# adaptateur_fusible.net
KiCad netlist of a schematic drawn in EAGLE
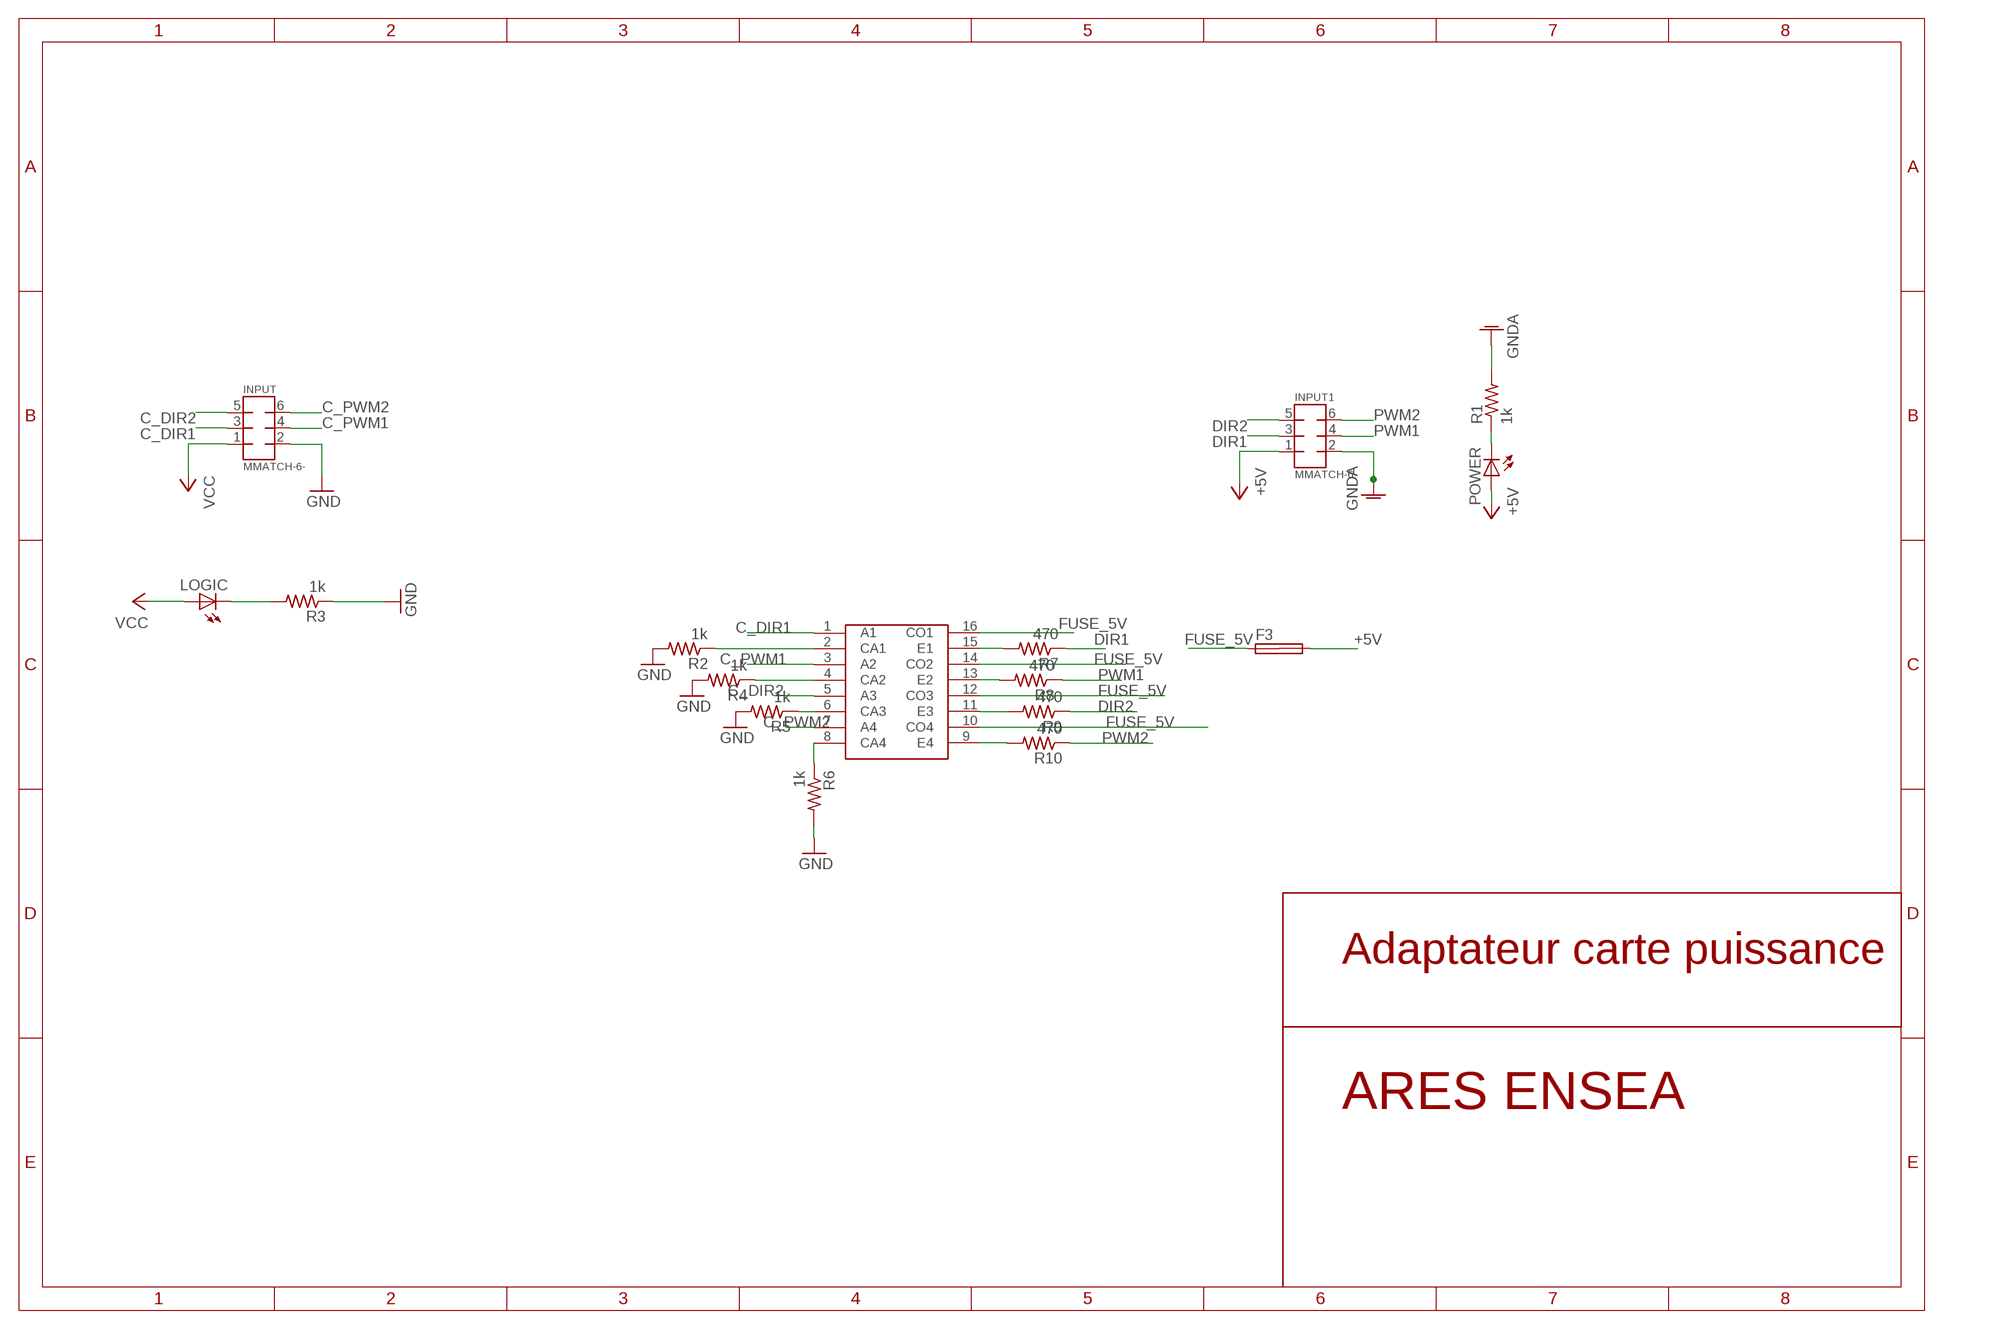
[diagram p0: schematic, sheet 1]

(export (version "E")
  (design (tool "Eeschema 10.0.6"))
  (components
    (comp (ref "F3")
      (value "SHK20Q")
      (footprint "eagle-import:SHK20Q")
      (libsource (lib "eagle-import") (part "SHK20Q"))
    )
    (comp (ref "INPUT")
      (value "MMATCH-6-")
      (footprint "eagle-import:AMP-215079-6")
      (libsource (lib "eagle-import") (part "MMATCH-6-"))
    )
    (comp (ref "INPUT1")
      (value "MMATCH-6-")
      (footprint "eagle-import:AMP-215079-6")
      (libsource (lib "eagle-import") (part "MMATCH-6-"))
    )
    (comp (ref "LOGIC")
      (value "LEDSML0805")
      (footprint "eagle-import:SML0805")
      (libsource (lib "eagle-import") (part "LEDSML0805"))
    )
    (comp (ref "POWER")
      (value "LEDSML0805")
      (footprint "eagle-import:SML0805")
      (libsource (lib "eagle-import") (part "LEDSML0805"))
    )
    (comp (ref "R1")
      (value "1k")
      (footprint "eagle-import:M0805")
      (libsource (lib "eagle-import") (part "R-US_M0805"))
    )
    (comp (ref "R2")
      (value "1k")
      (footprint "eagle-import:M0805")
      (libsource (lib "eagle-import") (part "R-US_M0805"))
    )
    (comp (ref "R3")
      (value "1k")
      (footprint "eagle-import:M0805")
      (libsource (lib "eagle-import") (part "R-US_M0805"))
    )
    (comp (ref "R4")
      (value "1k")
      (footprint "eagle-import:M0805")
      (libsource (lib "eagle-import") (part "R-US_M0805"))
    )
    (comp (ref "R5")
      (value "1k")
      (footprint "eagle-import:M0805")
      (libsource (lib "eagle-import") (part "R-US_M0805"))
    )
    (comp (ref "R6")
      (value "1k")
      (footprint "eagle-import:M0805")
      (libsource (lib "eagle-import") (part "R-US_M0805"))
    )
    (comp (ref "R7")
      (value "470")
      (footprint "eagle-import:M0805")
      (libsource (lib "eagle-import") (part "R-US_M0805"))
    )
    (comp (ref "R8")
      (value "470")
      (footprint "eagle-import:M0805")
      (libsource (lib "eagle-import") (part "R-US_M0805"))
    )
    (comp (ref "R9")
      (value "470")
      (footprint "eagle-import:M0805")
      (libsource (lib "eagle-import") (part "R-US_M0805"))
    )
    (comp (ref "R10")
      (value "470")
      (footprint "eagle-import:M0805")
      (libsource (lib "eagle-import") (part "R-US_M0805"))
    )
    (comp (ref "U$1")
      (value "ACPL-244")
      (footprint "eagle-import:ACPL-244")
      (libsource (lib "eagle-import") (part "ACPL-244"))
    )
  )
  (nets
    (net (code "1") (name "+5V") (class "Default")
      (node (ref "F3") (pin "2A") (pinfunction "2A_2A") (pintype "passive"))
      (node (ref "INPUT1") (pin "1") (pinfunction "3_1") (pintype "bidirectional"))
      (node (ref "POWER") (pin "A") (pinfunction "A_A") (pintype "passive"))
    )
    (net (code "2") (name "/C_DIR1") (class "Default")
      (node (ref "INPUT") (pin "3") (pinfunction "5_3") (pintype "bidirectional"))
      (node (ref "U$1") (pin "1") (pinfunction "A1_1") (pintype "bidirectional"))
    )
    (net (code "3") (name "/C_DIR2") (class "Default")
      (node (ref "INPUT") (pin "5") (pinfunction "7_5") (pintype "bidirectional"))
      (node (ref "U$1") (pin "5") (pinfunction "A3_5") (pintype "bidirectional"))
    )
    (net (code "4") (name "/C_PWM1") (class "Default")
      (node (ref "INPUT") (pin "4") (pinfunction "6_4") (pintype "bidirectional"))
      (node (ref "U$1") (pin "3") (pinfunction "A2_3") (pintype "bidirectional"))
    )
    (net (code "5") (name "/C_PWM2") (class "Default")
      (node (ref "INPUT") (pin "6") (pinfunction "8_6") (pintype "bidirectional"))
      (node (ref "U$1") (pin "7") (pinfunction "A4_7") (pintype "bidirectional"))
    )
    (net (code "6") (name "/DIR1") (class "Default")
      (node (ref "INPUT1") (pin "3") (pinfunction "5_3") (pintype "bidirectional"))
      (node (ref "R7") (pin "1") (pinfunction "1_1") (pintype "passive"))
    )
    (net (code "7") (name "/DIR2") (class "Default")
      (node (ref "INPUT1") (pin "5") (pinfunction "7_5") (pintype "bidirectional"))
      (node (ref "R9") (pin "1") (pinfunction "1_1") (pintype "passive"))
    )
    (net (code "8") (name "/FUSE_5V") (class "Default")
      (node (ref "F3") (pin "1A") (pinfunction "1A_1A") (pintype "passive"))
      (node (ref "U$1") (pin "10") (pinfunction "CO4_10") (pintype "bidirectional"))
      (node (ref "U$1") (pin "12") (pinfunction "CO3_12") (pintype "bidirectional"))
      (node (ref "U$1") (pin "14") (pinfunction "CO2_14") (pintype "bidirectional"))
      (node (ref "U$1") (pin "16") (pinfunction "CO1_16") (pintype "bidirectional"))
    )
    (net (code "9") (name "/PWM1") (class "Default")
      (node (ref "INPUT1") (pin "4") (pinfunction "6_4") (pintype "bidirectional"))
      (node (ref "R8") (pin "1") (pinfunction "1_1") (pintype "passive"))
    )
    (net (code "10") (name "/PWM2") (class "Default")
      (node (ref "INPUT1") (pin "6") (pinfunction "8_6") (pintype "bidirectional"))
      (node (ref "R10") (pin "1") (pinfunction "1_1") (pintype "passive"))
    )
    (net (code "11") (name "GND") (class "Default")
      (node (ref "INPUT") (pin "2") (pinfunction "4_2") (pintype "bidirectional"))
      (node (ref "R2") (pin "2") (pinfunction "2_2") (pintype "passive"))
      (node (ref "R3") (pin "1") (pinfunction "1_1") (pintype "passive"))
      (node (ref "R4") (pin "2") (pinfunction "2_2") (pintype "passive"))
      (node (ref "R5") (pin "2") (pinfunction "2_2") (pintype "passive"))
      (node (ref "R6") (pin "2") (pinfunction "2_2") (pintype "passive"))
    )
    (net (code "12") (name "GNDA") (class "Default")
      (node (ref "INPUT1") (pin "2") (pinfunction "4_2") (pintype "bidirectional"))
      (node (ref "R1") (pin "2") (pinfunction "2_2") (pintype "passive"))
    )
    (net (code "13") (name "Net-(LOGIC-PadC)") (class "Default")
      (node (ref "LOGIC") (pin "C") (pinfunction "C_C") (pintype "passive"))
      (node (ref "R3") (pin "2") (pinfunction "2_2") (pintype "passive"))
    )
    (net (code "14") (name "Net-(POWER-PadC)") (class "Default")
      (node (ref "POWER") (pin "C") (pinfunction "C_C") (pintype "passive"))
      (node (ref "R1") (pin "1") (pinfunction "1_1") (pintype "passive"))
    )
    (net (code "15") (name "Net-(U$1-CA1)") (class "Default")
      (node (ref "R2") (pin "1") (pinfunction "1_1") (pintype "passive"))
      (node (ref "U$1") (pin "2") (pinfunction "CA1_2") (pintype "bidirectional"))
    )
    (net (code "16") (name "Net-(U$1-CA2)") (class "Default")
      (node (ref "R4") (pin "1") (pinfunction "1_1") (pintype "passive"))
      (node (ref "U$1") (pin "4") (pinfunction "CA2_4") (pintype "bidirectional"))
    )
    (net (code "17") (name "Net-(U$1-CA3)") (class "Default")
      (node (ref "R5") (pin "1") (pinfunction "1_1") (pintype "passive"))
      (node (ref "U$1") (pin "6") (pinfunction "CA3_6") (pintype "bidirectional"))
    )
    (net (code "18") (name "Net-(U$1-CA4)") (class "Default")
      (node (ref "R6") (pin "1") (pinfunction "1_1") (pintype "passive"))
      (node (ref "U$1") (pin "8") (pinfunction "CA4_8") (pintype "bidirectional"))
    )
    (net (code "19") (name "Net-(U$1-E1)") (class "Default")
      (node (ref "R7") (pin "2") (pinfunction "2_2") (pintype "passive"))
      (node (ref "U$1") (pin "15") (pinfunction "E1_15") (pintype "bidirectional"))
    )
    (net (code "20") (name "Net-(U$1-E2)") (class "Default")
      (node (ref "R8") (pin "2") (pinfunction "2_2") (pintype "passive"))
      (node (ref "U$1") (pin "13") (pinfunction "E2_13") (pintype "bidirectional"))
    )
    (net (code "21") (name "Net-(U$1-E3)") (class "Default")
      (node (ref "R9") (pin "2") (pinfunction "2_2") (pintype "passive"))
      (node (ref "U$1") (pin "11") (pinfunction "E3_11") (pintype "bidirectional"))
    )
    (net (code "22") (name "Net-(U$1-E4)") (class "Default")
      (node (ref "R10") (pin "2") (pinfunction "2_2") (pintype "passive"))
      (node (ref "U$1") (pin "9") (pinfunction "E4_9") (pintype "bidirectional"))
    )
    (net (code "23") (name "VCC") (class "Default")
      (node (ref "INPUT") (pin "1") (pinfunction "3_1") (pintype "bidirectional"))
      (node (ref "LOGIC") (pin "A") (pinfunction "A_A") (pintype "passive"))
    )
    (net (code "24") (name "unconnected-(F3-Pad1B)") (class "Default")
      (node (ref "F3") (pin "1B") (pinfunction "1B_1B") (pintype "passive"))
    )
    (net (code "25") (name "unconnected-(F3-Pad2B)") (class "Default")
      (node (ref "F3") (pin "2B") (pinfunction "2B_2B") (pintype "passive"))
    )
  )
)
